# Sheet1.net
KiCad netlist of a schematic drawn in Altium Designer
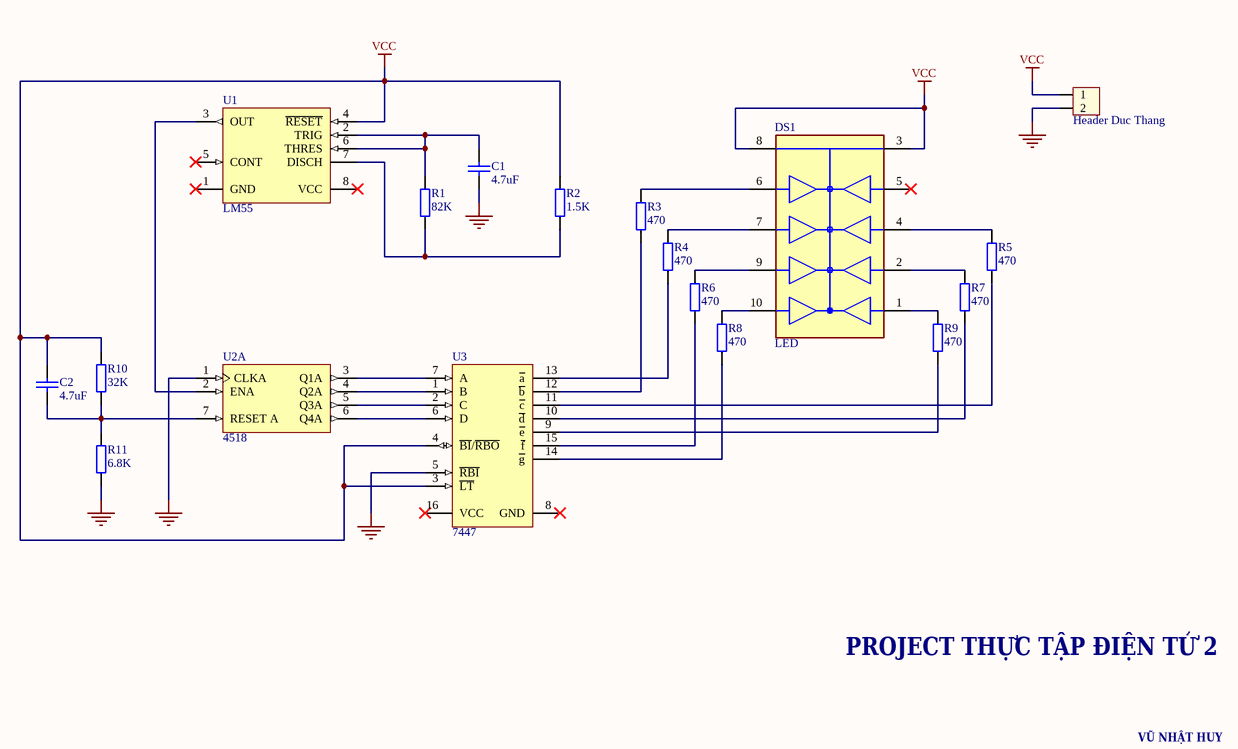
[diagram p0: Sheet1.SchDoc]

(export (version "E")
  (design (tool "Eeschema 10.0.6"))
  (components
    (comp (ref "C1")
      (value "4.7uF")
      (footprint "tu gom")
      (description "Cắm")
      (libsource (lib "Altium_Lib_by_KhueNguyenCreator") (part "Tu gom 472 50V"))
    )
    (comp (ref "C2")
      (value "4.7uF")
      (footprint "tu gom")
      (description "Cắm")
      (libsource (lib "Altium_Lib_by_KhueNguyenCreator") (part "Tu gom 472 50V"))
    )
    (comp (ref "DS1")
      (value "LED")
      (footprint "FP-HDSP-H153-MFG")
      (description "LED 7-SEG 14.2MM CC RED RHD RHD")
      (fields
        (field (name "OCTOPART") "https://octopart.com/hdsp-h153-broadcom-71129578")
        (field (name "MANUFACTURER PART NUMBER") "HDSP-H153")
      )
      (libsource (lib "Altium Content Vault") (part "84a80ac4071a6eb1a0df8b92a28a5e0"))
    )
    (comp (ref "H1")
      (value "Header Duc Thang")
      (footprint "VH3.96M-2")
      (description "Cắm")
      (libsource (lib "Altium_Lib_by_KhueNguyenCreator") (part "Header 2P VH3.96 Duc Thang"))
    )
    (comp (ref "R1")
      (value "82K")
      (footprint "RES_0805")
      (description "Resistor SMD 0805")
      (libsource (lib "Schematic-Lib-PhilsLab") (part "RES_0805"))
    )
    (comp (ref "R2")
      (value "1.5K")
      (footprint "RES_0805")
      (description "Resistor SMD 0805")
      (libsource (lib "Schematic-Lib-PhilsLab") (part "RES_0805"))
    )
    (comp (ref "R3")
      (value "470")
      (footprint "RES_0805")
      (description "Resistor SMD 0805")
      (libsource (lib "Schematic-Lib-PhilsLab") (part "RES_0805"))
    )
    (comp (ref "R4")
      (value "470")
      (footprint "RES_0805")
      (description "Resistor SMD 0805")
      (libsource (lib "Schematic-Lib-PhilsLab") (part "RES_0805"))
    )
    (comp (ref "R5")
      (value "470")
      (footprint "RES_0805")
      (description "Resistor SMD 0805")
      (libsource (lib "Schematic-Lib-PhilsLab") (part "RES_0805"))
    )
    (comp (ref "R6")
      (value "470")
      (footprint "RES_0805")
      (description "Resistor SMD 0805")
      (libsource (lib "Schematic-Lib-PhilsLab") (part "RES_0805"))
    )
    (comp (ref "R7")
      (value "470")
      (footprint "RES_0805")
      (description "Resistor SMD 0805")
      (libsource (lib "Schematic-Lib-PhilsLab") (part "RES_0805"))
    )
    (comp (ref "R8")
      (value "470")
      (footprint "RES_0805")
      (description "Resistor SMD 0805")
      (libsource (lib "Schematic-Lib-PhilsLab") (part "RES_0805"))
    )
    (comp (ref "R9")
      (value "470")
      (footprint "RES_0805")
      (description "Resistor SMD 0805")
      (libsource (lib "Schematic-Lib-PhilsLab") (part "RES_0805"))
    )
    (comp (ref "R10")
      (value "32K")
      (footprint "RES_0805")
      (description "Resistor SMD 0805")
      (libsource (lib "Schematic-Lib-PhilsLab") (part "RES_0805"))
    )
    (comp (ref "R11")
      (value "6.8K")
      (footprint "RES_0805")
      (description "Resistor SMD 0805")
      (libsource (lib "Schematic-Lib-PhilsLab") (part "RES_0805"))
    )
    (comp (ref "U1")
      (value "LM55")
      (footprint "P0008A")
      (description "Precision Timer, 4.5 to 16 V, 0 to 70 degC, 8-Pin DIP, Pb-Free, Tube")
      (fields (field (name "MANUFACTURER") "TexasInstruments"))
      (libsource (lib "Altium Content Vault") (part "TI-NE555-P8"))
    )
    (comp (ref "U2")
      (value "4518")
      (footprint "N0016A")
      (description "CMOS Dual BCD Up-Counter, N0016A, TUBE")
      (fields
        (field (name "MANUFACTURER") "Texas Instruments")
        (field (name "GENERIC PART NUMBER") "CD4518B")
      )
      (libsource (lib "Altium Content Vault") (part "TI-CD45XXB-16"))
    )
    (comp (ref "U3")
      (value "7447")
      (footprint "N0016A")
      (description "BCD-to-7-Segment Decoder / Driver, 4.75 to 5.25 V, 0 to 70 degC, 16-pin DIP (N16), Pb-Free (RoHS)")
      (fields (field (name "MANUFACTURER") "Texas Instruments") (field (name "PARTNUMBER") "SN7447AN"))
      (libsource (lib "Altium Content Vault") (part "TI-SNX4XX247-16"))
    )
  )
  (nets
    (net (code "1") (name "GND") (class "Default")
      (node (ref "C1") (pin "2") (pinfunction "2_2") (pintype "passive"))
      (node (ref "H1") (pin "2") (pinfunction "2_2") (pintype "passive"))
      (node (ref "R11") (pin "1") (pinfunction "1_1") (pintype "passive"))
      (node (ref "U2") (pin "1") (pinfunction "CLKA_1") (pintype "input"))
      (node (ref "U3") (pin "5") (pinfunction "~{RBI}_5") (pintype "input"))
    )
    (net (code "2") (name "Net-(DS1-ANODE_a)") (class "Default")
      (node (ref "DS1") (pin "7") (pinfunction "ANODE_a_7") (pintype "passive"))
      (node (ref "R4") (pin "2") (pinfunction "2_2") (pintype "passive"))
    )
    (net (code "3") (name "Net-(DS1-ANODE_b)") (class "Default")
      (node (ref "DS1") (pin "6") (pinfunction "ANODE_b_6") (pintype "passive"))
      (node (ref "R3") (pin "2") (pinfunction "2_2") (pintype "passive"))
    )
    (net (code "4") (name "Net-(DS1-ANODE_c)") (class "Default")
      (node (ref "DS1") (pin "4") (pinfunction "ANODE_c_4") (pintype "passive"))
      (node (ref "R5") (pin "1") (pinfunction "1_1") (pintype "passive"))
    )
    (net (code "5") (name "Net-(DS1-ANODE_d)") (class "Default")
      (node (ref "DS1") (pin "2") (pinfunction "ANODE_d_2") (pintype "passive"))
      (node (ref "R7") (pin "1") (pinfunction "1_1") (pintype "passive"))
    )
    (net (code "6") (name "Net-(DS1-ANODE_e)") (class "Default")
      (node (ref "DS1") (pin "1") (pinfunction "ANODE_e_1") (pintype "passive"))
      (node (ref "R9") (pin "1") (pinfunction "1_1") (pintype "passive"))
    )
    (net (code "7") (name "Net-(DS1-ANODE_f)") (class "Default")
      (node (ref "DS1") (pin "9") (pinfunction "ANODE_f_9") (pintype "passive"))
      (node (ref "R6") (pin "2") (pinfunction "2_2") (pintype "passive"))
    )
    (net (code "8") (name "Net-(DS1-ANODE_g)") (class "Default")
      (node (ref "DS1") (pin "10") (pinfunction "ANODE_g_10") (pintype "passive"))
      (node (ref "R8") (pin "2") (pinfunction "2_2") (pintype "passive"))
    )
    (net (code "9") (name "Net-(U1-DISCH)") (class "Default")
      (node (ref "R1") (pin "1") (pinfunction "1_1") (pintype "passive"))
      (node (ref "R2") (pin "1") (pinfunction "1_1") (pintype "passive"))
      (node (ref "U1") (pin "7") (pinfunction "DISCH_7") (pintype "open_collector"))
    )
    (net (code "10") (name "Net-(U1-OUT)") (class "Default")
      (node (ref "U1") (pin "3") (pinfunction "OUT_3") (pintype "output"))
      (node (ref "U2") (pin "2") (pinfunction "ENA_2") (pintype "input"))
    )
    (net (code "11") (name "Net-(U1-THRES)") (class "Default")
      (node (ref "C1") (pin "1") (pinfunction "1_1") (pintype "passive"))
      (node (ref "R1") (pin "2") (pinfunction "2_2") (pintype "passive"))
      (node (ref "U1") (pin "2") (pinfunction "TRIG_2") (pintype "input"))
      (node (ref "U1") (pin "6") (pinfunction "THRES_6") (pintype "input"))
    )
    (net (code "12") (name "Net-(U2A-Q1A)") (class "Default")
      (node (ref "U2") (pin "3") (pinfunction "Q1A_3") (pintype "output"))
      (node (ref "U3") (pin "7") (pinfunction "A_7") (pintype "input"))
    )
    (net (code "13") (name "Net-(U2A-Q2A)") (class "Default")
      (node (ref "U2") (pin "4") (pinfunction "Q2A_4") (pintype "output"))
      (node (ref "U3") (pin "1") (pinfunction "B_1") (pintype "input"))
    )
    (net (code "14") (name "Net-(U2A-Q3A)") (class "Default")
      (node (ref "U2") (pin "5") (pinfunction "Q3A_5") (pintype "output"))
      (node (ref "U3") (pin "2") (pinfunction "C_2") (pintype "input"))
    )
    (net (code "15") (name "Net-(U2A-Q4A)") (class "Default")
      (node (ref "U2") (pin "6") (pinfunction "Q4A_6") (pintype "output"))
      (node (ref "U3") (pin "6") (pinfunction "D_6") (pintype "input"))
    )
    (net (code "16") (name "Net-(U2A-RESET_A)") (class "Default")
      (node (ref "C2") (pin "2") (pinfunction "2_2") (pintype "passive"))
      (node (ref "R10") (pin "1") (pinfunction "1_1") (pintype "passive"))
      (node (ref "R11") (pin "2") (pinfunction "2_2") (pintype "passive"))
      (node (ref "U2") (pin "7") (pinfunction "RESET_A_7") (pintype "input"))
    )
    (net (code "17") (name "Net-(U3-~{a})") (class "Default")
      (node (ref "R4") (pin "1") (pinfunction "1_1") (pintype "passive"))
      (node (ref "U3") (pin "13") (pinfunction "~{a}_13") (pintype "open_collector"))
    )
    (net (code "18") (name "Net-(U3-~{b})") (class "Default")
      (node (ref "R3") (pin "1") (pinfunction "1_1") (pintype "passive"))
      (node (ref "U3") (pin "12") (pinfunction "~{b}_12") (pintype "open_collector"))
    )
    (net (code "19") (name "Net-(U3-~{c})") (class "Default")
      (node (ref "R5") (pin "2") (pinfunction "2_2") (pintype "passive"))
      (node (ref "U3") (pin "11") (pinfunction "~{c}_11") (pintype "open_collector"))
    )
    (net (code "20") (name "Net-(U3-~{d})") (class "Default")
      (node (ref "R7") (pin "2") (pinfunction "2_2") (pintype "passive"))
      (node (ref "U3") (pin "10") (pinfunction "~{d}_10") (pintype "open_collector"))
    )
    (net (code "21") (name "Net-(U3-~{e})") (class "Default")
      (node (ref "R9") (pin "2") (pinfunction "2_2") (pintype "passive"))
      (node (ref "U3") (pin "9") (pinfunction "~{e}_9") (pintype "open_collector"))
    )
    (net (code "22") (name "Net-(U3-~{f})") (class "Default")
      (node (ref "R6") (pin "1") (pinfunction "1_1") (pintype "passive"))
      (node (ref "U3") (pin "15") (pinfunction "~{f}_15") (pintype "open_collector"))
    )
    (net (code "23") (name "Net-(U3-~{g})") (class "Default")
      (node (ref "R8") (pin "1") (pinfunction "1_1") (pintype "passive"))
      (node (ref "U3") (pin "14") (pinfunction "~{g}_14") (pintype "open_collector"))
    )
    (net (code "24") (name "VCC") (class "Default")
      (node (ref "C2") (pin "1") (pinfunction "1_1") (pintype "passive"))
      (node (ref "DS1") (pin "3") (pinfunction "C_3") (pintype "passive"))
      (node (ref "DS1") (pin "8") (pinfunction "C_8") (pintype "passive"))
      (node (ref "H1") (pin "1") (pinfunction "1_1") (pintype "passive"))
      (node (ref "R10") (pin "2") (pinfunction "2_2") (pintype "passive"))
      (node (ref "R2") (pin "2") (pinfunction "2_2") (pintype "passive"))
      (node (ref "U1") (pin "4") (pinfunction "~{RESET}_4") (pintype "input"))
      (node (ref "U3") (pin "3") (pinfunction "~{LT}_3") (pintype "input"))
      (node (ref "U3") (pin "4") (pinfunction "~{BI}/~{RBO}_4") (pintype "bidirectional"))
    )
    (net (code "25") (name "unconnected-(DS1-ANODE_DP-Pad5)") (class "Default")
      (node (ref "DS1") (pin "5") (pinfunction "ANODE_DP_5") (pintype "passive+no_connect"))
    )
    (net (code "26") (name "unconnected-(U1-CONT-Pad5)") (class "Default")
      (node (ref "U1") (pin "5") (pinfunction "CONT_5") (pintype "input+no_connect"))
    )
    (net (code "27") (name "unconnected-(U1-GND-Pad1)") (class "Default")
      (node (ref "U1") (pin "1") (pinfunction "GND_1") (pintype "power_in+no_connect"))
    )
    (net (code "28") (name "unconnected-(U1-VCC-Pad8)") (class "Default")
      (node (ref "U1") (pin "8") (pinfunction "VCC_8") (pintype "power_in+no_connect"))
    )
    (net (code "29") (name "unconnected-(U3-GND-Pad8)") (class "Default")
      (node (ref "U3") (pin "8") (pinfunction "GND_8") (pintype "power_in+no_connect"))
    )
    (net (code "30") (name "unconnected-(U3-VCC-Pad16)") (class "Default")
      (node (ref "U3") (pin "16") (pinfunction "VCC_16") (pintype "power_in+no_connect"))
    )
  )
)
